# FlexEMG_v0r0_RADIO.net
KiCad netlist of a schematic drawn in Altium Designer
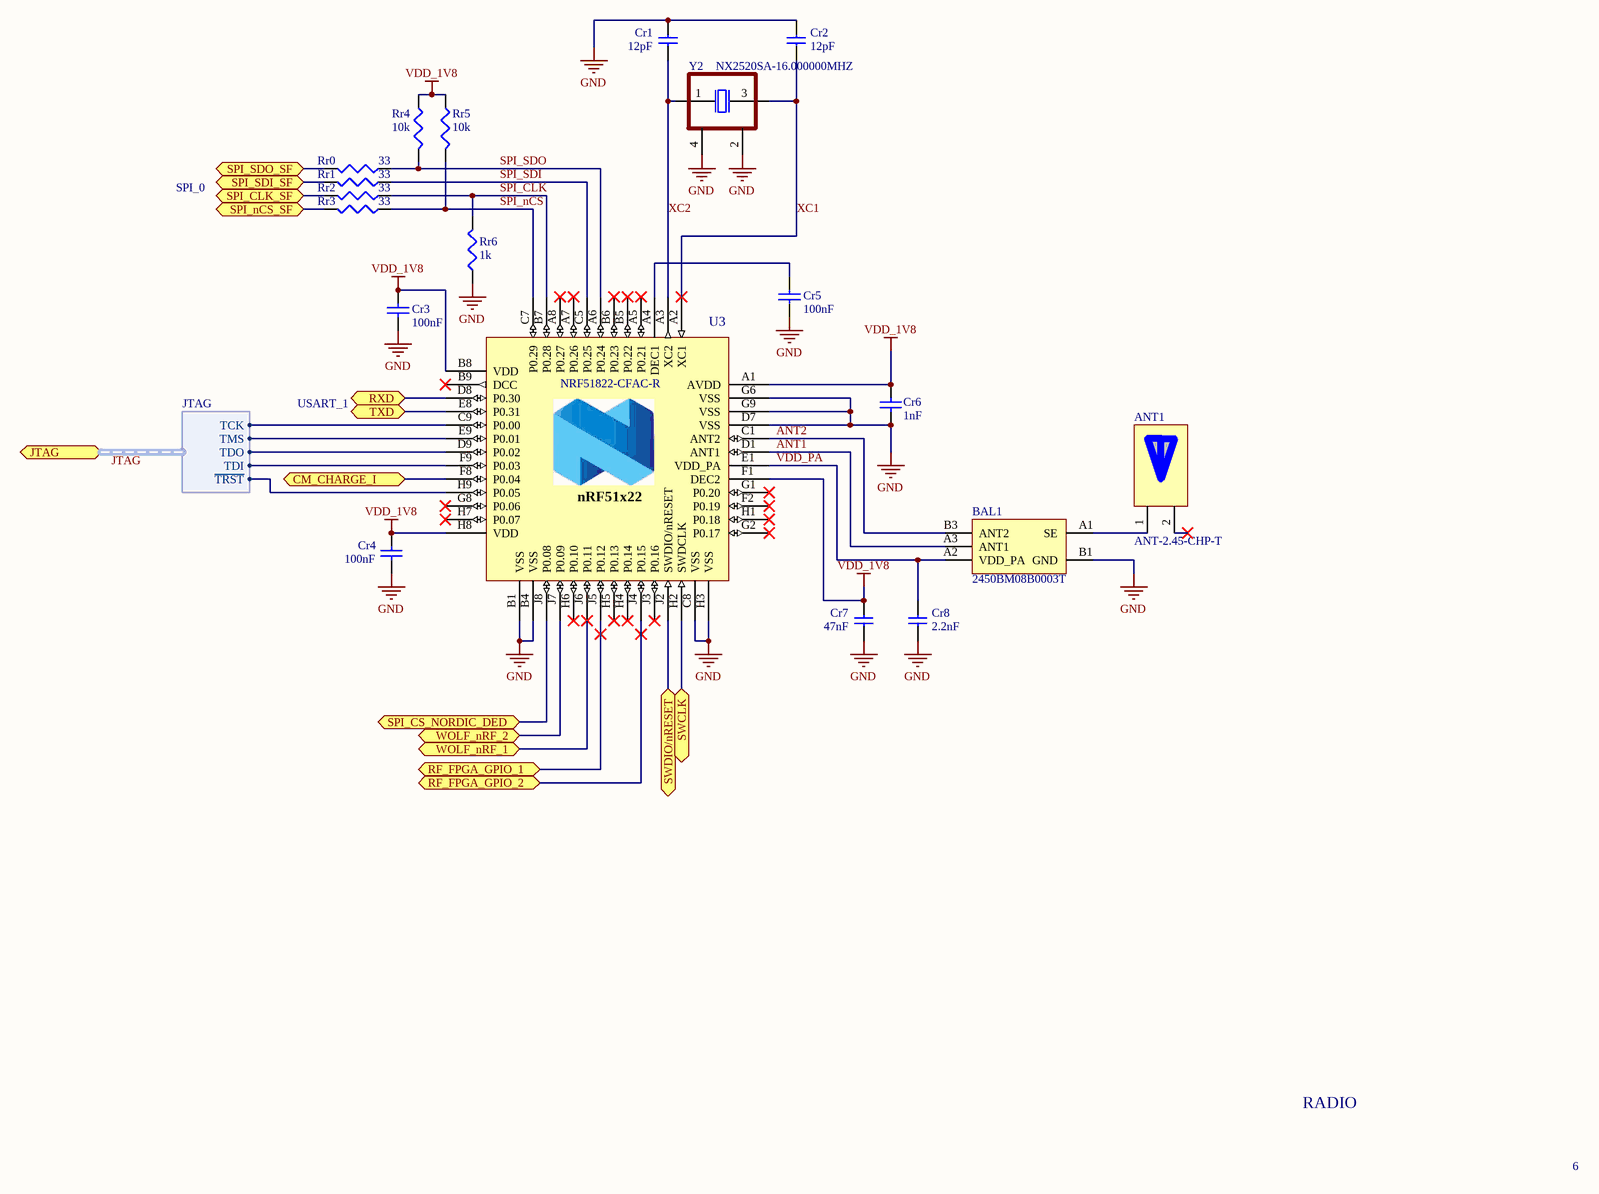
[diagram p0: FlexEMG_v0r0_RADIO.SchDoc]

(export (version "E")
  (design (tool "Eeschema 10.0.6"))
  (components
    (comp (ref "ANT1")
      (value "ANT-2.45-CHP-T")
      (footprint "ANTENNACHIP")
      (description "ANT 2.4GHZ 802.11 BLUETOOTH SMD")
      (fields (field (name "MANUFACTURER") "Linx"))
      (libsource (lib "CM") (part "Linx ANT-2.45-CHP-x"))
    )
    (comp (ref "BAL1")
      (value "2450BM08B0003T")
      (footprint "BALUN_PACKAGE")
      (description "BALUN 2.4GHZ")
      (fields (field (name "MANUFACTURER") "Johnson"))
      (libsource (lib "CM") (part "BAL_NRF02D3"))
    )
    (comp (ref "Cr1")
      (value "12pF")
      (footprint "c0402-Murata-GR")
      (description "CAP CER 12PF 50V NP0 0402")
      (fields (field (name "MANUFACTURER") "Murata") (field (name "Comment") "GRM1555C1H120FA01D"))
      (libsource (lib "Custom") (part "CAP_0402"))
    )
    (comp (ref "Cr2")
      (value "12pF")
      (footprint "c0402-Murata-GR")
      (description "CAP CER 12PF 50V NP0 0402")
      (fields (field (name "MANUFACTURER") "Murata") (field (name "Comment") "GRM1555C1H120FA01D"))
      (libsource (lib "Custom") (part "CAP_0402"))
    )
    (comp (ref "Cr3")
      (value "100nF")
      (footprint "0402_ss")
      (description "CAP CER 0.1UF 16V X7S 0201")
      (fields (field (name "MANUFACTURER") "Murata") (field (name "Comment") "GRM033R6YA104KE14D"))
      (libsource (lib "Custom") (part "Cap"))
    )
    (comp (ref "Cr4")
      (value "100nF")
      (footprint "c0402-Murata-GR")
      (description "CAP CER 0.1UF 50V X5R 0402")
      (fields (field (name "MANUFACTURER") "Murata") (field (name "Comment") "GRM155R61H104KE19D"))
      (libsource (lib "Custom") (part "Cap"))
    )
    (comp (ref "Cr5")
      (value "100nF")
      (footprint "0201")
      (description "CAP CER 0.1UF 16V X7S 0201")
      (fields (field (name "MANUFACTURER") "Murata") (field (name "Comment") "GRM033R6YA104KE14D"))
      (libsource (lib "Custom") (part "Cap"))
    )
    (comp (ref "Cr6")
      (value "1nF")
      (footprint "c0402-Murata-GR")
      (description "CAP CER 1000PF 50V X5R 0402")
      (fields (field (name "MANUFACTURER") "Murata") (field (name "Comment") "GRM155R61H102KA01D"))
      (libsource (lib "Custom") (part "Cap"))
    )
    (comp (ref "Cr7")
      (value "47nF")
      (footprint "c0402-Murata-GR")
      (description "CAP CER 0.047UF 25V X7R 0402 10%")
      (fields (field (name "MANUFACTURER") "Murata") (field (name "Comment") "GRM155R71E473KA88D"))
      (libsource (lib "Custom") (part "CAP_0402"))
    )
    (comp (ref "Cr8")
      (value "2.2nF")
      (footprint "c0402-Murata-GR")
      (description "CAP CER 2200PF 50V X7R 0402")
      (fields (field (name "MANUFACTURER") "Murata"))
      (libsource (lib "Custom") (part "CAP_0402"))
    )
    (comp (ref "Rr0")
      (value "33")
      (footprint "0201")
      (description "RES SMD 33 OHM 1% 1/10W 0402")
      (fields (field (name "MANUFACTURER") "Panasonic") (field (name "POWER") "1/5W"))
      (libsource (lib "Custom") (part "Resistor"))
    )
    (comp (ref "Rr1")
      (value "33")
      (footprint "0201")
      (description "RES SMD 33 OHM 1% 1/10W 0402")
      (fields (field (name "MANUFACTURER") "Panasonic") (field (name "POWER") "1/5W"))
      (libsource (lib "Custom") (part "Resistor"))
    )
    (comp (ref "Rr2")
      (value "33")
      (footprint "0201")
      (description "RES SMD 33 OHM 1% 1/10W 0402")
      (fields (field (name "MANUFACTURER") "Panasonic") (field (name "POWER") "1/5W"))
      (libsource (lib "Custom") (part "Resistor"))
    )
    (comp (ref "Rr3")
      (value "33")
      (footprint "0201")
      (description "RES SMD 33 OHM 1% 1/10W 0402")
      (fields (field (name "MANUFACTURER") "Panasonic") (field (name "POWER") "1/5W"))
      (libsource (lib "Custom") (part "Resistor"))
    )
    (comp (ref "Rr4")
      (value "10k")
      (footprint "0201")
      (description "RES SMD 10K OHM 1% 1/10W 0402")
      (fields (field (name "MANUFACTURER") "Panasonic") (field (name "POWER") "1/10W"))
      (libsource (lib "Custom") (part "Resistor"))
    )
    (comp (ref "Rr5")
      (value "10k")
      (footprint "0402_p")
      (description "RES SMD 10K OHM 1% 1/10W 0402")
      (fields (field (name "MANUFACTURER") "Panasonic") (field (name "POWER") "1/10W"))
      (libsource (lib "Custom") (part "Resistor"))
    )
    (comp (ref "Rr6")
      (value "1k")
      (footprint "0201")
      (description "RES SMD 1K OHM 1% 1/10W 0402")
      (fields (field (name "MANUFACTURER") "Panasonic") (field (name "POWER") "1/10W"))
      (libsource (lib "Custom") (part "Resistor"))
    )
    (comp (ref "U3")
      (value "NRF51822-CFAC-R")
      (footprint "CM001:BGA_NORDIC")
      (description "IC SOC 2.4GHZ MULTIPROTO 62WLCS")
      (fields (field (name "MANUFACTURER") "Nordic"))
      (libsource (lib "CM") (part "nRF51822"))
    )
    (comp (ref "Y2")
      (value "NX2520SA-16.000000MHZ")
      (footprint "XOSC_4PIN")
      (description "CRYSTAL 16.0000MHZ 10PF SMD")
      (fields (field (name "MANUFACTURER") "NDK"))
      (libsource (lib "CM") (part "XOSC"))
    )
  )
  (nets
    (net (code "2") (name "/ANT1") (class "Default")
      (node (ref "BAL1") (pin "A3") (pinfunction "ANT1_A3") (pintype "passive"))
      (node (ref "U3") (pin "D1") (pinfunction "ANT1_D1") (pintype "bidirectional"))
    )
    (net (code "3") (name "/ANT2") (class "Default")
      (node (ref "BAL1") (pin "B3") (pinfunction "ANT2_B3") (pintype "passive"))
      (node (ref "U3") (pin "C1") (pinfunction "ANT2_C1") (pintype "bidirectional"))
    )
    (net (code "4") (name "/CM_CHARGE_I") (class "Default")
      (node (ref "U3") (pin "F8") (pinfunction "P0.04_F8") (pintype "bidirectional"))
    )
    (net (code "6") (name "/RF_FPGA_GPIO_1") (class "Default")
      (node (ref "U3") (pin "J5") (pinfunction "P0.12_J5") (pintype "bidirectional+no_connect"))
    )
    (net (code "7") (name "/RF_FPGA_GPIO_2") (class "Default")
      (node (ref "U3") (pin "J4") (pinfunction "P0.15_J4") (pintype "bidirectional+no_connect"))
    )
    (net (code "8") (name "/RXD") (class "Default")
      (node (ref "U3") (pin "D8") (pinfunction "P0.30_D8") (pintype "bidirectional"))
    )
    (net (code "9") (name "/SPI_CLK") (class "Default")
      (node (ref "Rr2") (pin "1") (pinfunction "1_1") (pintype "passive"))
      (node (ref "Rr6") (pin "2") (pinfunction "2_2") (pintype "passive"))
      (node (ref "U3") (pin "B7") (pinfunction "P0.28_B7") (pintype "bidirectional"))
    )
    (net (code "10") (name "/SPI_CLK_SF") (class "Default")
      (node (ref "Rr2") (pin "2") (pinfunction "2_2") (pintype "passive"))
    )
    (net (code "11") (name "/SPI_CS_NORDIC_DED") (class "Default")
      (node (ref "U3") (pin "J8") (pinfunction "P0.08_J8") (pintype "bidirectional"))
    )
    (net (code "12") (name "/SPI_SDI") (class "Default")
      (node (ref "Rr1") (pin "1") (pinfunction "1_1") (pintype "passive"))
      (node (ref "U3") (pin "C5") (pinfunction "P0.25_C5") (pintype "bidirectional"))
    )
    (net (code "13") (name "/SPI_SDI_SF") (class "Default")
      (node (ref "Rr1") (pin "2") (pinfunction "2_2") (pintype "passive"))
    )
    (net (code "14") (name "/SPI_SDO") (class "Default")
      (node (ref "Rr0") (pin "1") (pinfunction "1_1") (pintype "passive"))
      (node (ref "Rr4") (pin "2") (pinfunction "2_2") (pintype "passive"))
      (node (ref "U3") (pin "A6") (pinfunction "P0.24_A6") (pintype "bidirectional"))
    )
    (net (code "15") (name "/SPI_SDO_SF") (class "Default")
      (node (ref "Rr0") (pin "2") (pinfunction "2_2") (pintype "passive"))
    )
    (net (code "16") (name "/SPI_nCS") (class "Default")
      (node (ref "Rr3") (pin "1") (pinfunction "1_1") (pintype "passive"))
      (node (ref "Rr5") (pin "2") (pinfunction "2_2") (pintype "passive"))
      (node (ref "U3") (pin "C7") (pinfunction "P0.29_C7") (pintype "bidirectional"))
    )
    (net (code "17") (name "/SPI_nCS_SF") (class "Default")
      (node (ref "Rr3") (pin "2") (pinfunction "2_2") (pintype "passive"))
    )
    (net (code "18") (name "/SWCLK") (class "Default")
      (node (ref "U3") (pin "H2") (pinfunction "SWDCLK_H2") (pintype "input"))
    )
    (net (code "19") (name "/SWDIO{slash}nRESET") (class "Default")
      (node (ref "U3") (pin "J2") (pinfunction "SWDIO/nRESET_J2") (pintype "input"))
    )
    (net (code "20") (name "/TCK") (class "Default")
      (node (ref "U3") (pin "C9") (pinfunction "P0.00_C9") (pintype "bidirectional"))
    )
    (net (code "21") (name "/TDI") (class "Default")
      (node (ref "U3") (pin "F9") (pinfunction "P0.03_F9") (pintype "bidirectional"))
    )
    (net (code "22") (name "/TDO") (class "Default")
      (node (ref "U3") (pin "D9") (pinfunction "P0.02_D9") (pintype "bidirectional"))
    )
    (net (code "23") (name "/TMS") (class "Default")
      (node (ref "U3") (pin "E9") (pinfunction "P0.01_E9") (pintype "bidirectional"))
    )
    (net (code "24") (name "/TXD") (class "Default")
      (node (ref "U3") (pin "E8") (pinfunction "P0.31_E8") (pintype "bidirectional"))
    )
    (net (code "25") (name "/VDD_PA") (class "Default")
      (node (ref "BAL1") (pin "A2") (pinfunction "VDD_PA_A2") (pintype "passive"))
      (node (ref "Cr8") (pin "2") (pinfunction "2_2") (pintype "passive"))
      (node (ref "U3") (pin "E1") (pinfunction "VDD_PA_E1") (pintype "power_in"))
    )
    (net (code "26") (name "/WOLF_nRF_1") (class "Default")
      (node (ref "U3") (pin "J6") (pinfunction "P0.11_J6") (pintype "bidirectional+no_connect"))
    )
    (net (code "27") (name "/WOLF_nRF_2") (class "Default")
      (node (ref "U3") (pin "J7") (pinfunction "P0.09_J7") (pintype "bidirectional"))
    )
    (net (code "28") (name "/XC1") (class "Default")
      (node (ref "Cr2") (pin "1") (pinfunction "1_1") (pintype "passive"))
      (node (ref "U3") (pin "A2") (pinfunction "XC1_A2") (pintype "input"))
      (node (ref "Y2") (pin "3") (pinfunction "out_3") (pintype "passive"))
    )
    (net (code "29") (name "/XC2") (class "Default")
      (node (ref "Cr1") (pin "1") (pinfunction "1_1") (pintype "passive"))
      (node (ref "U3") (pin "A3") (pinfunction "XC2_A3") (pintype "output"))
      (node (ref "Y2") (pin "1") (pinfunction "inp_1") (pintype "passive"))
    )
    (net (code "30") (name "/~{TRST}") (class "Default")
      (node (ref "U3") (pin "H9") (pinfunction "P0.05_H9") (pintype "bidirectional"))
    )
    (net (code "31") (name "GND") (class "Default")
      (node (ref "BAL1") (pin "B1") (pinfunction "GND_B1") (pintype "passive"))
      (node (ref "Cr1") (pin "2") (pinfunction "2_2") (pintype "passive"))
      (node (ref "Cr2") (pin "2") (pinfunction "2_2") (pintype "passive"))
      (node (ref "Cr3") (pin "1") (pinfunction "1_1") (pintype "passive"))
      (node (ref "Cr4") (pin "1") (pinfunction "1_1") (pintype "passive"))
      (node (ref "Cr5") (pin "1") (pinfunction "1_1") (pintype "passive"))
      (node (ref "Cr6") (pin "2") (pinfunction "2_2") (pintype "passive"))
      (node (ref "Cr7") (pin "1") (pinfunction "1_1") (pintype "passive"))
      (node (ref "Cr8") (pin "1") (pinfunction "1_1") (pintype "passive"))
      (node (ref "Rr6") (pin "1") (pinfunction "1_1") (pintype "passive"))
      (node (ref "U3") (pin "B1") (pinfunction "VSS_B1") (pintype "power_in"))
      (node (ref "U3") (pin "B4") (pinfunction "VSS_B4") (pintype "power_in"))
      (node (ref "U3") (pin "C8") (pinfunction "VSS_C8") (pintype "power_in"))
      (node (ref "U3") (pin "D7") (pinfunction "VSS_D7") (pintype "power_in"))
      (node (ref "U3") (pin "G6") (pinfunction "VSS_G6") (pintype "power_in"))
      (node (ref "U3") (pin "G9") (pinfunction "VSS_G9") (pintype "power_in"))
      (node (ref "U3") (pin "H3") (pinfunction "VSS_H3") (pintype "power_in"))
      (node (ref "Y2") (pin "2") (pinfunction "GND_2") (pintype "passive"))
      (node (ref "Y2") (pin "4") (pinfunction "GND_4") (pintype "passive"))
    )
    (net (code "32") (name "Net-(ANT1-IN)") (class "Default")
      (node (ref "ANT1") (pin "1") (pinfunction "IN_1") (pintype "passive"))
      (node (ref "BAL1") (pin "A1") (pinfunction "SE_A1") (pintype "passive"))
    )
    (net (code "33") (name "Net-(U3-DEC1)") (class "Default")
      (node (ref "Cr5") (pin "2") (pinfunction "2_2") (pintype "passive"))
      (node (ref "U3") (pin "A4") (pinfunction "DEC1_A4") (pintype "power_in"))
    )
    (net (code "34") (name "VDD_1V8") (class "Default")
      (node (ref "Cr3") (pin "2") (pinfunction "2_2") (pintype "passive"))
      (node (ref "Cr4") (pin "2") (pinfunction "2_2") (pintype "passive"))
      (node (ref "Cr6") (pin "1") (pinfunction "1_1") (pintype "passive"))
      (node (ref "Cr7") (pin "2") (pinfunction "2_2") (pintype "passive"))
      (node (ref "Rr4") (pin "1") (pinfunction "1_1") (pintype "passive"))
      (node (ref "Rr5") (pin "1") (pinfunction "1_1") (pintype "passive"))
      (node (ref "U3") (pin "A1") (pinfunction "AVDD_A1") (pintype "power_in"))
      (node (ref "U3") (pin "B8") (pinfunction "VDD_B8") (pintype "power_in"))
      (node (ref "U3") (pin "F1") (pinfunction "DEC2_F1") (pintype "power_in"))
      (node (ref "U3") (pin "H8") (pinfunction "VDD_H8") (pintype "power_in"))
    )
    (net (code "35") (name "unconnected-(ANT1-NC-Pad2)") (class "Default")
      (node (ref "ANT1") (pin "2") (pinfunction "NC_2") (pintype "passive+no_connect"))
    )
    (net (code "36") (name "unconnected-(U3-DCC-PadB9)") (class "Default")
      (node (ref "U3") (pin "B9") (pinfunction "DCC_B9") (pintype "output+no_connect"))
    )
    (net (code "37") (name "unconnected-(U3-P0.06-PadG8)") (class "Default")
      (node (ref "U3") (pin "G8") (pinfunction "P0.06_G8") (pintype "bidirectional+no_connect"))
    )
    (net (code "38") (name "unconnected-(U3-P0.07-PadH7)") (class "Default")
      (node (ref "U3") (pin "H7") (pinfunction "P0.07_H7") (pintype "bidirectional+no_connect"))
    )
    (net (code "39") (name "unconnected-(U3-P0.10-PadH6)") (class "Default")
      (node (ref "U3") (pin "H6") (pinfunction "P0.10_H6") (pintype "bidirectional+no_connect"))
    )
    (net (code "40") (name "unconnected-(U3-P0.13-PadH5)") (class "Default")
      (node (ref "U3") (pin "H5") (pinfunction "P0.13_H5") (pintype "bidirectional+no_connect"))
    )
    (net (code "41") (name "unconnected-(U3-P0.14-PadH4)") (class "Default")
      (node (ref "U3") (pin "H4") (pinfunction "P0.14_H4") (pintype "bidirectional+no_connect"))
    )
    (net (code "42") (name "unconnected-(U3-P0.16-PadJ3)") (class "Default")
      (node (ref "U3") (pin "J3") (pinfunction "P0.16_J3") (pintype "bidirectional+no_connect"))
    )
    (net (code "43") (name "unconnected-(U3-P0.17-PadG2)") (class "Default")
      (node (ref "U3") (pin "G2") (pinfunction "P0.17_G2") (pintype "bidirectional+no_connect"))
    )
    (net (code "44") (name "unconnected-(U3-P0.18-PadH1)") (class "Default")
      (node (ref "U3") (pin "H1") (pinfunction "P0.18_H1") (pintype "bidirectional+no_connect"))
    )
    (net (code "45") (name "unconnected-(U3-P0.19-PadF2)") (class "Default")
      (node (ref "U3") (pin "F2") (pinfunction "P0.19_F2") (pintype "bidirectional+no_connect"))
    )
    (net (code "46") (name "unconnected-(U3-P0.20-PadG1)") (class "Default")
      (node (ref "U3") (pin "G1") (pinfunction "P0.20_G1") (pintype "bidirectional+no_connect"))
    )
    (net (code "47") (name "unconnected-(U3-P0.21-PadA5)") (class "Default")
      (node (ref "U3") (pin "A5") (pinfunction "P0.21_A5") (pintype "bidirectional+no_connect"))
    )
    (net (code "48") (name "unconnected-(U3-P0.22-PadB5)") (class "Default")
      (node (ref "U3") (pin "B5") (pinfunction "P0.22_B5") (pintype "bidirectional+no_connect"))
    )
    (net (code "49") (name "unconnected-(U3-P0.23-PadB6)") (class "Default")
      (node (ref "U3") (pin "B6") (pinfunction "P0.23_B6") (pintype "bidirectional+no_connect"))
    )
    (net (code "50") (name "unconnected-(U3-P0.26-PadA7)") (class "Default")
      (node (ref "U3") (pin "A7") (pinfunction "P0.26_A7") (pintype "bidirectional+no_connect"))
    )
    (net (code "51") (name "unconnected-(U3-P0.27-PadA8)") (class "Default")
      (node (ref "U3") (pin "A8") (pinfunction "P0.27_A8") (pintype "bidirectional+no_connect"))
    )
  )
)
